# FX2_USB_Microcontroller.net
KiCad netlist of a schematic drawn in Altium Designer
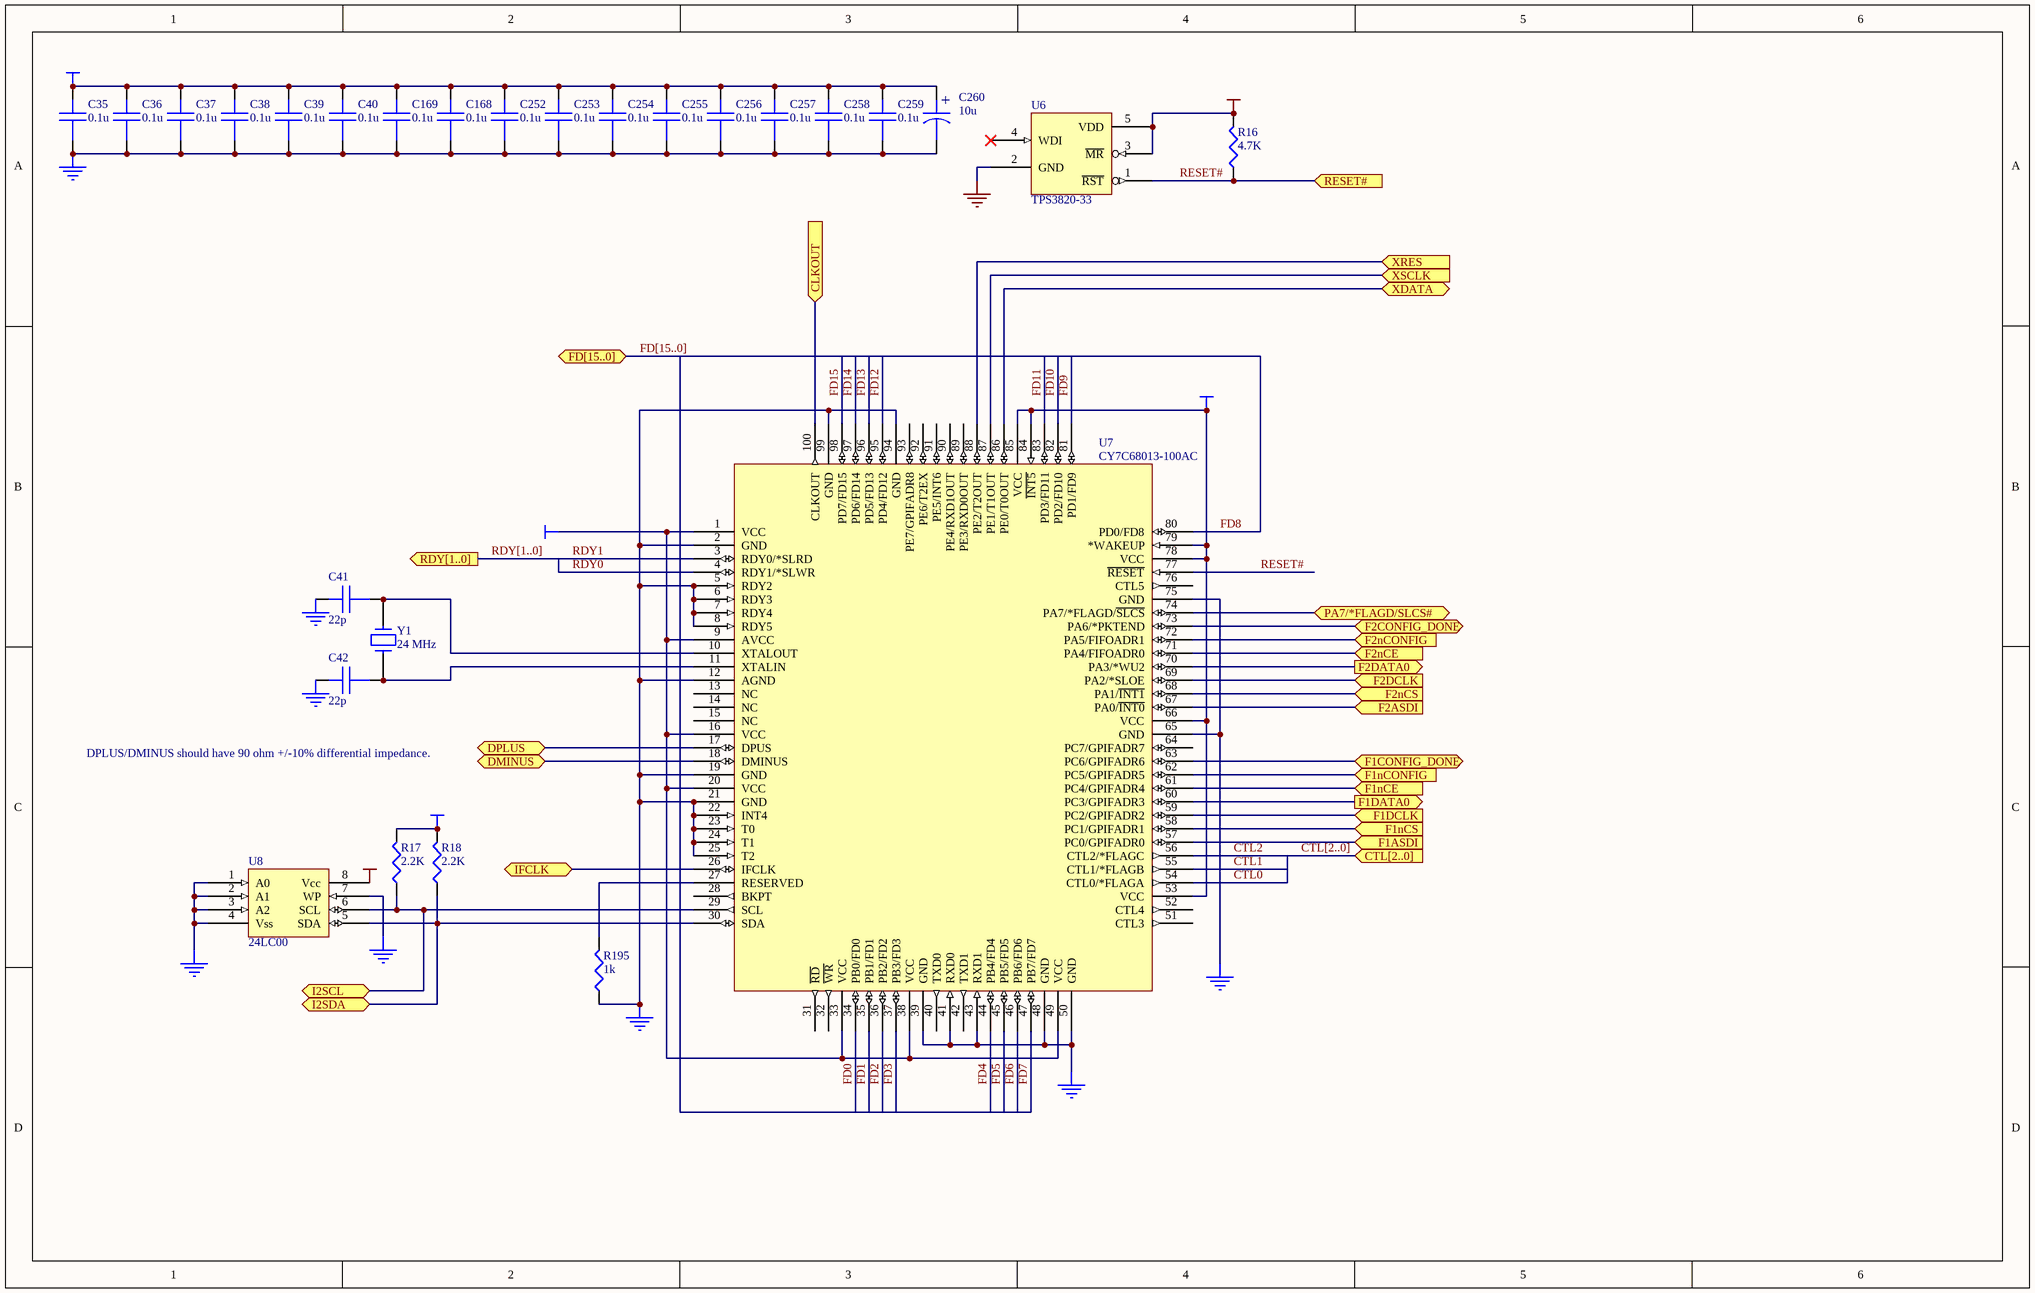
[diagram p0: FX2 USB Microcontroller.SchDoc]

(export (version "E")
  (design (tool "Eeschema 10.0.6"))
  (components
    (comp (ref "C35")
      (value "~")
      (footprint "0603")
      (description "SMT CAP")
      (libsource (lib "Cypress Molson") (part "CAP"))
    )
    (comp (ref "C36")
      (value "~")
      (footprint "0603")
      (description "SMT CAP")
      (libsource (lib "Cypress Molson") (part "CAP"))
    )
    (comp (ref "C37")
      (value "~")
      (footprint "0603")
      (description "SMT CAP")
      (libsource (lib "Cypress Molson") (part "CAP"))
    )
    (comp (ref "C38")
      (value "~")
      (footprint "0603")
      (description "SMT CAP")
      (libsource (lib "Cypress Molson") (part "CAP"))
    )
    (comp (ref "C39")
      (value "~")
      (footprint "0603")
      (description "SMT CAP")
      (libsource (lib "Cypress Molson") (part "CAP"))
    )
    (comp (ref "C40")
      (value "~")
      (footprint "0603")
      (description "SMT CAP")
      (libsource (lib "Cypress Molson") (part "CAP"))
    )
    (comp (ref "C41")
      (value "~")
      (footprint "0603")
      (description "SMT CAP")
      (libsource (lib "Cypress Molson") (part "CAP"))
    )
    (comp (ref "C42")
      (value "~")
      (footprint "0603")
      (description "SMT CAP")
      (libsource (lib "Cypress Molson") (part "CAP"))
    )
    (comp (ref "C168")
      (value "~")
      (footprint "0603")
      (description "SMT CAP")
      (libsource (lib "Cypress Molson") (part "CAP"))
    )
    (comp (ref "C169")
      (value "~")
      (footprint "0603")
      (description "SMT CAP")
      (libsource (lib "Cypress Molson") (part "CAP"))
    )
    (comp (ref "C252")
      (value "~")
      (footprint "0603")
      (description "SMT CAP")
      (libsource (lib "Cypress Molson") (part "CAP"))
    )
    (comp (ref "C253")
      (value "~")
      (footprint "0603")
      (description "SMT CAP")
      (libsource (lib "Cypress Molson") (part "CAP"))
    )
    (comp (ref "C254")
      (value "~")
      (footprint "0603")
      (description "SMT CAP")
      (libsource (lib "Cypress Molson") (part "CAP"))
    )
    (comp (ref "C255")
      (value "~")
      (footprint "0603")
      (description "SMT CAP")
      (libsource (lib "Cypress Molson") (part "CAP"))
    )
    (comp (ref "C256")
      (value "~")
      (footprint "0603")
      (description "SMT CAP")
      (libsource (lib "Cypress Molson") (part "CAP"))
    )
    (comp (ref "C257")
      (value "~")
      (footprint "0603")
      (description "SMT CAP")
      (libsource (lib "Cypress Molson") (part "CAP"))
    )
    (comp (ref "C258")
      (value "~")
      (footprint "0603")
      (description "SMT CAP")
      (libsource (lib "Cypress Molson") (part "CAP"))
    )
    (comp (ref "C259")
      (value "~")
      (footprint "0603")
      (description "SMT CAP")
      (libsource (lib "Cypress Molson") (part "CAP"))
    )
    (comp (ref "C260")
      (value "10u")
      (footprint "6032")
      (libsource (lib "Cypress Molson") (part "CAPACITOR POL"))
    )
    (comp (ref "R16") (value "4.7K") (footprint "0603") (libsource (lib "*") (part "RES1")))
    (comp (ref "R17") (value "2.2K") (footprint "0603") (libsource (lib "Cypress Molson") (part "RES1")))
    (comp (ref "R18") (value "2.2K") (footprint "0603") (libsource (lib "Cypress Molson") (part "RES1")))
    (comp (ref "R195") (value "1k") (footprint "0603") (libsource (lib "Cypress Molson") (part "RES1")))
    (comp (ref "U6")
      (value "TPS3820-33")
      (footprint "DBV")
      (description "Processor Supervisory Circuit")
      (libsource (lib "*") (part "TPS3820"))
    )
    (comp (ref "U7") (value "~") (libsource (lib "Cypress Molson") (part "CY7C68013-100AC")))
    (comp (ref "U8")
      (value "24LC00")
      (footprint "SO-8")
      (description "128-bit I2C Bus Serial EEPROM")
      (libsource (lib "Cypress Molson") (part "24LC00"))
    )
    (comp (ref "Y1") (value "24 MHz") (description "Crystal") (libsource (lib "Schematic") (part "CRYSTAL")))
  )
  (nets
    (net (code "1") (name "+3.3V") (class "Default")
      (node (ref "C168") (pin "1") (pinfunction "1_1") (pintype "passive"))
      (node (ref "C169") (pin "1") (pinfunction "1_1") (pintype "passive"))
      (node (ref "C252") (pin "1") (pinfunction "1_1") (pintype "passive"))
      (node (ref "C253") (pin "1") (pinfunction "1_1") (pintype "passive"))
      (node (ref "C254") (pin "1") (pinfunction "1_1") (pintype "passive"))
      (node (ref "C255") (pin "1") (pinfunction "1_1") (pintype "passive"))
      (node (ref "C256") (pin "1") (pinfunction "1_1") (pintype "passive"))
      (node (ref "C257") (pin "1") (pinfunction "1_1") (pintype "passive"))
      (node (ref "C258") (pin "1") (pinfunction "1_1") (pintype "passive"))
      (node (ref "C259") (pin "1") (pinfunction "1_1") (pintype "passive"))
      (node (ref "C260") (pin "1") (pinfunction "1_1") (pintype "passive"))
      (node (ref "C35") (pin "1") (pinfunction "1_1") (pintype "passive"))
      (node (ref "C36") (pin "1") (pinfunction "1_1") (pintype "passive"))
      (node (ref "C37") (pin "1") (pinfunction "1_1") (pintype "passive"))
      (node (ref "C38") (pin "1") (pinfunction "1_1") (pintype "passive"))
      (node (ref "C39") (pin "1") (pinfunction "1_1") (pintype "passive"))
      (node (ref "C40") (pin "1") (pinfunction "1_1") (pintype "passive"))
      (node (ref "R16") (pin "2") (pintype "passive"))
      (node (ref "R17") (pin "2") (pintype "passive"))
      (node (ref "R18") (pin "2") (pintype "passive"))
      (node (ref "U6") (pin "3") (pinfunction "~{MR}_3") (pintype "input"))
      (node (ref "U6") (pin "5") (pinfunction "VDD_5") (pintype "power_in"))
      (node (ref "U7") (pin "1") (pinfunction "VCC_1") (pintype "power_in"))
      (node (ref "U7") (pin "16") (pinfunction "VCC_16") (pintype "power_in"))
      (node (ref "U7") (pin "20") (pinfunction "VCC_20") (pintype "power_in"))
      (node (ref "U7") (pin "33") (pinfunction "VCC_33") (pintype "power_in"))
      (node (ref "U7") (pin "38") (pinfunction "VCC_38") (pintype "power_in"))
      (node (ref "U7") (pin "49") (pinfunction "VCC_49") (pintype "power_in"))
      (node (ref "U7") (pin "53") (pinfunction "VCC_53") (pintype "power_in"))
      (node (ref "U7") (pin "66") (pinfunction "VCC_66") (pintype "power_in"))
      (node (ref "U7") (pin "78") (pinfunction "VCC_78") (pintype "power_in"))
      (node (ref "U7") (pin "79") (pinfunction "*WAKEUP_79") (pintype "input"))
      (node (ref "U7") (pin "84") (pinfunction "~{INT5}_84") (pintype "input"))
      (node (ref "U7") (pin "85") (pinfunction "VCC_85") (pintype "power_in"))
      (node (ref "U7") (pin "9") (pinfunction "AVCC_9") (pintype "power_in"))
      (node (ref "U8") (pin "8") (pinfunction "Vcc_8") (pintype "power_in"))
    )
    (net (code "2") (name "/CLKOUT") (class "Default")
      (node (ref "U7") (pin "100") (pinfunction "CLKOUT_100") (pintype "output"))
    )
    (net (code "3") (name "/CTL0") (class "Default")
      (node (ref "U7") (pin "54") (pinfunction "CTL0/*FLAGA_54") (pintype "output"))
    )
    (net (code "4") (name "/CTL1") (class "Default")
      (node (ref "U7") (pin "55") (pinfunction "CTL1/*FLAGB_55") (pintype "output"))
    )
    (net (code "5") (name "/CTL2") (class "Default")
      (node (ref "U7") (pin "56") (pinfunction "CTL2/*FLAGC_56") (pintype "output"))
    )
    (net (code "7") (name "/DMINUS") (class "Default")
      (node (ref "U7") (pin "18") (pinfunction "DMINUS_18") (pintype "bidirectional"))
    )
    (net (code "8") (name "/DPLUS") (class "Default")
      (node (ref "U7") (pin "17") (pinfunction "DPUS_17") (pintype "bidirectional"))
    )
    (net (code "9") (name "/F1ASDI") (class "Default")
      (node (ref "U7") (pin "57") (pinfunction "PC0/GPIFADR0_57") (pintype "bidirectional"))
    )
    (net (code "10") (name "/F1CONFIG_DONE") (class "Default")
      (node (ref "U7") (pin "63") (pinfunction "PC6/GPIFADR6_63") (pintype "bidirectional"))
    )
    (net (code "11") (name "/F1DATA0") (class "Default")
      (node (ref "U7") (pin "60") (pinfunction "PC3/GPIFADR3_60") (pintype "bidirectional"))
    )
    (net (code "12") (name "/F1DCLK") (class "Default")
      (node (ref "U7") (pin "59") (pinfunction "PC2/GPIFADR2_59") (pintype "bidirectional"))
    )
    (net (code "13") (name "/F1nCE") (class "Default")
      (node (ref "U7") (pin "61") (pinfunction "PC4/GPIFADR4_61") (pintype "bidirectional"))
    )
    (net (code "14") (name "/F1nCONFIG") (class "Default")
      (node (ref "U7") (pin "62") (pinfunction "PC5/GPIFADR5_62") (pintype "bidirectional"))
    )
    (net (code "15") (name "/F1nCS") (class "Default")
      (node (ref "U7") (pin "58") (pinfunction "PC1/GPIFADR1_58") (pintype "bidirectional"))
    )
    (net (code "16") (name "/F2ASDI") (class "Default")
      (node (ref "U7") (pin "67") (pinfunction "PA0/~{INT0}_67") (pintype "bidirectional"))
    )
    (net (code "17") (name "/F2CONFIG_DONE") (class "Default")
      (node (ref "U7") (pin "73") (pinfunction "PA6/*PKTEND_73") (pintype "bidirectional"))
    )
    (net (code "18") (name "/F2DATA0") (class "Default")
      (node (ref "U7") (pin "70") (pinfunction "PA3/*WU2_70") (pintype "bidirectional"))
    )
    (net (code "19") (name "/F2DCLK") (class "Default")
      (node (ref "U7") (pin "69") (pinfunction "PA2/*SLOE_69") (pintype "bidirectional"))
    )
    (net (code "20") (name "/F2nCE") (class "Default")
      (node (ref "U7") (pin "71") (pinfunction "PA4/FIFOADR0_71") (pintype "bidirectional"))
    )
    (net (code "21") (name "/F2nCONFIG") (class "Default")
      (node (ref "U7") (pin "72") (pinfunction "PA5/FIFOADR1_72") (pintype "bidirectional"))
    )
    (net (code "22") (name "/F2nCS") (class "Default")
      (node (ref "U7") (pin "68") (pinfunction "PA1/~{INT1}_68") (pintype "bidirectional"))
    )
    (net (code "23") (name "/FD0") (class "Default")
      (node (ref "U7") (pin "34") (pinfunction "PB0/FD0_34") (pintype "bidirectional"))
    )
    (net (code "24") (name "/FD1") (class "Default")
      (node (ref "U7") (pin "35") (pinfunction "PB1/FD1_35") (pintype "bidirectional"))
    )
    (net (code "25") (name "/FD2") (class "Default")
      (node (ref "U7") (pin "36") (pinfunction "PB2/FD2_36") (pintype "bidirectional"))
    )
    (net (code "26") (name "/FD3") (class "Default")
      (node (ref "U7") (pin "37") (pinfunction "PB3/FD3_37") (pintype "bidirectional"))
    )
    (net (code "27") (name "/FD4") (class "Default")
      (node (ref "U7") (pin "44") (pinfunction "PB4/FD4_44") (pintype "bidirectional"))
    )
    (net (code "28") (name "/FD5") (class "Default")
      (node (ref "U7") (pin "45") (pinfunction "PB5/FD5_45") (pintype "bidirectional"))
    )
    (net (code "29") (name "/FD6") (class "Default")
      (node (ref "U7") (pin "46") (pinfunction "PB6/FD6_46") (pintype "bidirectional"))
    )
    (net (code "30") (name "/FD7") (class "Default")
      (node (ref "U7") (pin "47") (pinfunction "PB7/FD7_47") (pintype "bidirectional"))
    )
    (net (code "31") (name "/FD8") (class "Default")
      (node (ref "U7") (pin "80") (pinfunction "PD0/FD8_80") (pintype "bidirectional"))
    )
    (net (code "32") (name "/FD9") (class "Default")
      (node (ref "U7") (pin "81") (pinfunction "PD1/FD9_81") (pintype "bidirectional"))
    )
    (net (code "33") (name "/FD10") (class "Default")
      (node (ref "U7") (pin "82") (pinfunction "PD2/FD10_82") (pintype "bidirectional"))
    )
    (net (code "34") (name "/FD11") (class "Default")
      (node (ref "U7") (pin "83") (pinfunction "PD3/FD11_83") (pintype "bidirectional"))
    )
    (net (code "35") (name "/FD12") (class "Default")
      (node (ref "U7") (pin "95") (pinfunction "PD4/FD12_95") (pintype "bidirectional"))
    )
    (net (code "36") (name "/FD13") (class "Default")
      (node (ref "U7") (pin "96") (pinfunction "PD5/FD13_96") (pintype "bidirectional"))
    )
    (net (code "37") (name "/FD14") (class "Default")
      (node (ref "U7") (pin "97") (pinfunction "PD6/FD14_97") (pintype "bidirectional"))
    )
    (net (code "38") (name "/FD15") (class "Default")
      (node (ref "U7") (pin "98") (pinfunction "PD7/FD15_98") (pintype "bidirectional"))
    )
    (net (code "40") (name "/I2SCL") (class "Default")
      (node (ref "R17") (pin "1") (pintype "passive"))
      (node (ref "U7") (pin "29") (pinfunction "SCL_29") (pintype "output"))
      (node (ref "U8") (pin "6") (pinfunction "SCL_6") (pintype "bidirectional"))
    )
    (net (code "41") (name "/I2SDA") (class "Default")
      (node (ref "R18") (pin "1") (pintype "passive"))
      (node (ref "U7") (pin "30") (pinfunction "SDA_30") (pintype "bidirectional"))
      (node (ref "U8") (pin "5") (pinfunction "SDA_5") (pintype "bidirectional"))
    )
    (net (code "42") (name "/IFCLK") (class "Default")
      (node (ref "U7") (pin "26") (pinfunction "IFCLK_26") (pintype "bidirectional"))
    )
    (net (code "43") (name "/PA7{slash}*FLAGD{slash}SLCS#") (class "Default")
      (node (ref "U7") (pin "74") (pinfunction "PA7/*FLAGD/~{SLCS}_74") (pintype "bidirectional"))
    )
    (net (code "44") (name "/RDY0") (class "Default")
      (node (ref "U7") (pin "4") (pinfunction "RDY1/*SLWR_4") (pintype "bidirectional"))
    )
    (net (code "45") (name "/RDY1") (class "Default")
      (node (ref "U7") (pin "3") (pinfunction "RDY0/*SLRD_3") (pintype "bidirectional"))
    )
    (net (code "47") (name "/RESET#") (class "Default")
      (node (ref "R16") (pin "1") (pintype "passive"))
      (node (ref "U6") (pin "1") (pinfunction "~{RST}_1") (pintype "output"))
      (node (ref "U7") (pin "77") (pinfunction "~{RESET}_77") (pintype "input"))
    )
    (net (code "48") (name "/XDATA") (class "Default")
      (node (ref "U7") (pin "86") (pinfunction "PE0/T0OUT_86") (pintype "bidirectional"))
    )
    (net (code "49") (name "/XRES") (class "Default")
      (node (ref "U7") (pin "88") (pinfunction "PE2/T2OUT_88") (pintype "bidirectional"))
    )
    (net (code "50") (name "/XSCLK") (class "Default")
      (node (ref "U7") (pin "87") (pinfunction "PE1/T1OUT_87") (pintype "bidirectional"))
    )
    (net (code "51") (name "GND") (class "Default")
      (node (ref "C168") (pin "2") (pinfunction "2_2") (pintype "passive"))
      (node (ref "C169") (pin "2") (pinfunction "2_2") (pintype "passive"))
      (node (ref "C252") (pin "2") (pinfunction "2_2") (pintype "passive"))
      (node (ref "C253") (pin "2") (pinfunction "2_2") (pintype "passive"))
      (node (ref "C254") (pin "2") (pinfunction "2_2") (pintype "passive"))
      (node (ref "C255") (pin "2") (pinfunction "2_2") (pintype "passive"))
      (node (ref "C256") (pin "2") (pinfunction "2_2") (pintype "passive"))
      (node (ref "C257") (pin "2") (pinfunction "2_2") (pintype "passive"))
      (node (ref "C258") (pin "2") (pinfunction "2_2") (pintype "passive"))
      (node (ref "C259") (pin "2") (pinfunction "2_2") (pintype "passive"))
      (node (ref "C260") (pin "2") (pinfunction "2_2") (pintype "passive"))
      (node (ref "C35") (pin "2") (pinfunction "2_2") (pintype "passive"))
      (node (ref "C36") (pin "2") (pinfunction "2_2") (pintype "passive"))
      (node (ref "C37") (pin "2") (pinfunction "2_2") (pintype "passive"))
      (node (ref "C38") (pin "2") (pinfunction "2_2") (pintype "passive"))
      (node (ref "C39") (pin "2") (pinfunction "2_2") (pintype "passive"))
      (node (ref "C40") (pin "2") (pinfunction "2_2") (pintype "passive"))
      (node (ref "C41") (pin "1") (pinfunction "1_1") (pintype "passive"))
      (node (ref "C42") (pin "1") (pinfunction "1_1") (pintype "passive"))
      (node (ref "R195") (pin "1") (pintype "passive"))
      (node (ref "U6") (pin "2") (pinfunction "GND_2") (pintype "power_in"))
      (node (ref "U7") (pin "12") (pinfunction "AGND_12") (pintype "power_in"))
      (node (ref "U7") (pin "19") (pinfunction "GND_19") (pintype "power_in"))
      (node (ref "U7") (pin "2") (pinfunction "GND_2") (pintype "power_in"))
      (node (ref "U7") (pin "21") (pinfunction "GND_21") (pintype "power_in"))
      (node (ref "U7") (pin "22") (pinfunction "INT4_22") (pintype "input"))
      (node (ref "U7") (pin "23") (pinfunction "T0_23") (pintype "input"))
      (node (ref "U7") (pin "24") (pinfunction "T1_24") (pintype "input"))
      (node (ref "U7") (pin "25") (pinfunction "T2_25") (pintype "input"))
      (node (ref "U7") (pin "39") (pinfunction "GND_39") (pintype "power_in"))
      (node (ref "U7") (pin "41") (pinfunction "RXD0_41") (pintype "input"))
      (node (ref "U7") (pin "43") (pinfunction "RXD1_43") (pintype "input"))
      (node (ref "U7") (pin "48") (pinfunction "GND_48") (pintype "power_in"))
      (node (ref "U7") (pin "5") (pinfunction "RDY2_5") (pintype "input"))
      (node (ref "U7") (pin "50") (pinfunction "GND_50") (pintype "power_in"))
      (node (ref "U7") (pin "6") (pinfunction "RDY3_6") (pintype "input"))
      (node (ref "U7") (pin "65") (pinfunction "GND_65") (pintype "power_in"))
      (node (ref "U7") (pin "7") (pinfunction "RDY4_7") (pintype "input"))
      (node (ref "U7") (pin "75") (pinfunction "GND_75") (pintype "power_in"))
      (node (ref "U7") (pin "8") (pinfunction "RDY5_8") (pintype "input"))
      (node (ref "U7") (pin "94") (pinfunction "GND_94") (pintype "power_in"))
      (node (ref "U7") (pin "99") (pinfunction "GND_99") (pintype "power_in"))
      (node (ref "U8") (pin "1") (pinfunction "A0_1") (pintype "input"))
      (node (ref "U8") (pin "2") (pinfunction "A1_2") (pintype "input"))
      (node (ref "U8") (pin "3") (pinfunction "A2_3") (pintype "input"))
      (node (ref "U8") (pin "4") (pinfunction "Vss_4") (pintype "power_in"))
      (node (ref "U8") (pin "7") (pinfunction "WP_7") (pintype "input"))
    )
    (net (code "52") (name "Net-(U7-RESERVED)") (class "Default")
      (node (ref "R195") (pin "2") (pintype "passive"))
      (node (ref "U7") (pin "27") (pinfunction "RESERVED_27") (pintype "tri_state"))
    )
    (net (code "53") (name "Net-(U7-XTALIN)") (class "Default")
      (node (ref "C42") (pin "2") (pinfunction "2_2") (pintype "passive"))
      (node (ref "U7") (pin "11") (pinfunction "XTALIN_11") (pintype "passive"))
      (node (ref "Y1") (pin "1") (pinfunction "1_1") (pintype "passive"))
    )
    (net (code "54") (name "Net-(U7-XTALOUT)") (class "Default")
      (node (ref "C41") (pin "2") (pinfunction "2_2") (pintype "passive"))
      (node (ref "U7") (pin "10") (pinfunction "XTALOUT_10") (pintype "passive"))
      (node (ref "Y1") (pin "2") (pinfunction "2_2") (pintype "passive"))
    )
    (net (code "55") (name "unconnected-(U6-WDI-Pad4)") (class "Default")
      (node (ref "U6") (pin "4") (pinfunction "WDI_4") (pintype "input+no_connect"))
    )
    (net (code "56") (name "unconnected-(U7-BKPT-Pad28)") (class "Default")
      (node (ref "U7") (pin "28") (pinfunction "BKPT_28") (pintype "output"))
    )
    (net (code "57") (name "unconnected-(U7-CTL3-Pad51)") (class "Default")
      (node (ref "U7") (pin "51") (pinfunction "CTL3_51") (pintype "output"))
    )
    (net (code "58") (name "unconnected-(U7-CTL4-Pad52)") (class "Default")
      (node (ref "U7") (pin "52") (pinfunction "CTL4_52") (pintype "output"))
    )
    (net (code "59") (name "unconnected-(U7-CTL5-Pad76)") (class "Default")
      (node (ref "U7") (pin "76") (pinfunction "CTL5_76") (pintype "output"))
    )
    (net (code "60") (name "unconnected-(U7-NC-Pad13)") (class "Default")
      (node (ref "U7") (pin "13") (pinfunction "NC_13") (pintype "tri_state"))
    )
    (net (code "61") (name "unconnected-(U7-NC-Pad14)") (class "Default")
      (node (ref "U7") (pin "14") (pinfunction "NC_14") (pintype "tri_state"))
    )
    (net (code "62") (name "unconnected-(U7-NC-Pad15)") (class "Default")
      (node (ref "U7") (pin "15") (pinfunction "NC_15") (pintype "tri_state"))
    )
    (net (code "63") (name "unconnected-(U7-PC7{slash}GPIFADR7-Pad64)") (class "Default")
      (node (ref "U7") (pin "64") (pinfunction "PC7/GPIFADR7_64") (pintype "bidirectional"))
    )
    (net (code "64") (name "unconnected-(U7-PE3{slash}RXD0OUT-Pad89)") (class "Default")
      (node (ref "U7") (pin "89") (pinfunction "PE3/RXD0OUT_89") (pintype "bidirectional"))
    )
    (net (code "65") (name "unconnected-(U7-PE4{slash}RXD1OUT-Pad90)") (class "Default")
      (node (ref "U7") (pin "90") (pinfunction "PE4/RXD1OUT_90") (pintype "bidirectional"))
    )
    (net (code "66") (name "unconnected-(U7-PE5{slash}INT6-Pad91)") (class "Default")
      (node (ref "U7") (pin "91") (pinfunction "PE5/INT6_91") (pintype "bidirectional"))
    )
    (net (code "67") (name "unconnected-(U7-PE6{slash}T2EX-Pad92)") (class "Default")
      (node (ref "U7") (pin "92") (pinfunction "PE6/T2EX_92") (pintype "bidirectional"))
    )
    (net (code "68") (name "unconnected-(U7-PE7{slash}GPIFADR8-Pad93)") (class "Default")
      (node (ref "U7") (pin "93") (pinfunction "PE7/GPIFADR8_93") (pintype "bidirectional"))
    )
    (net (code "69") (name "unconnected-(U7-TXD0-Pad40)") (class "Default")
      (node (ref "U7") (pin "40") (pinfunction "TXD0_40") (pintype "output"))
    )
    (net (code "70") (name "unconnected-(U7-TXD1-Pad42)") (class "Default")
      (node (ref "U7") (pin "42") (pinfunction "TXD1_42") (pintype "output"))
    )
    (net (code "71") (name "unconnected-(U7-~{RD}-Pad31)") (class "Default")
      (node (ref "U7") (pin "31") (pinfunction "~{RD}_31") (pintype "output"))
    )
    (net (code "72") (name "unconnected-(U7-~{WR}-Pad32)") (class "Default")
      (node (ref "U7") (pin "32") (pinfunction "~{WR}_32") (pintype "output"))
    )
  )
)
